# DNVT3.net
KiCad netlist of a schematic drawn in EAGLE
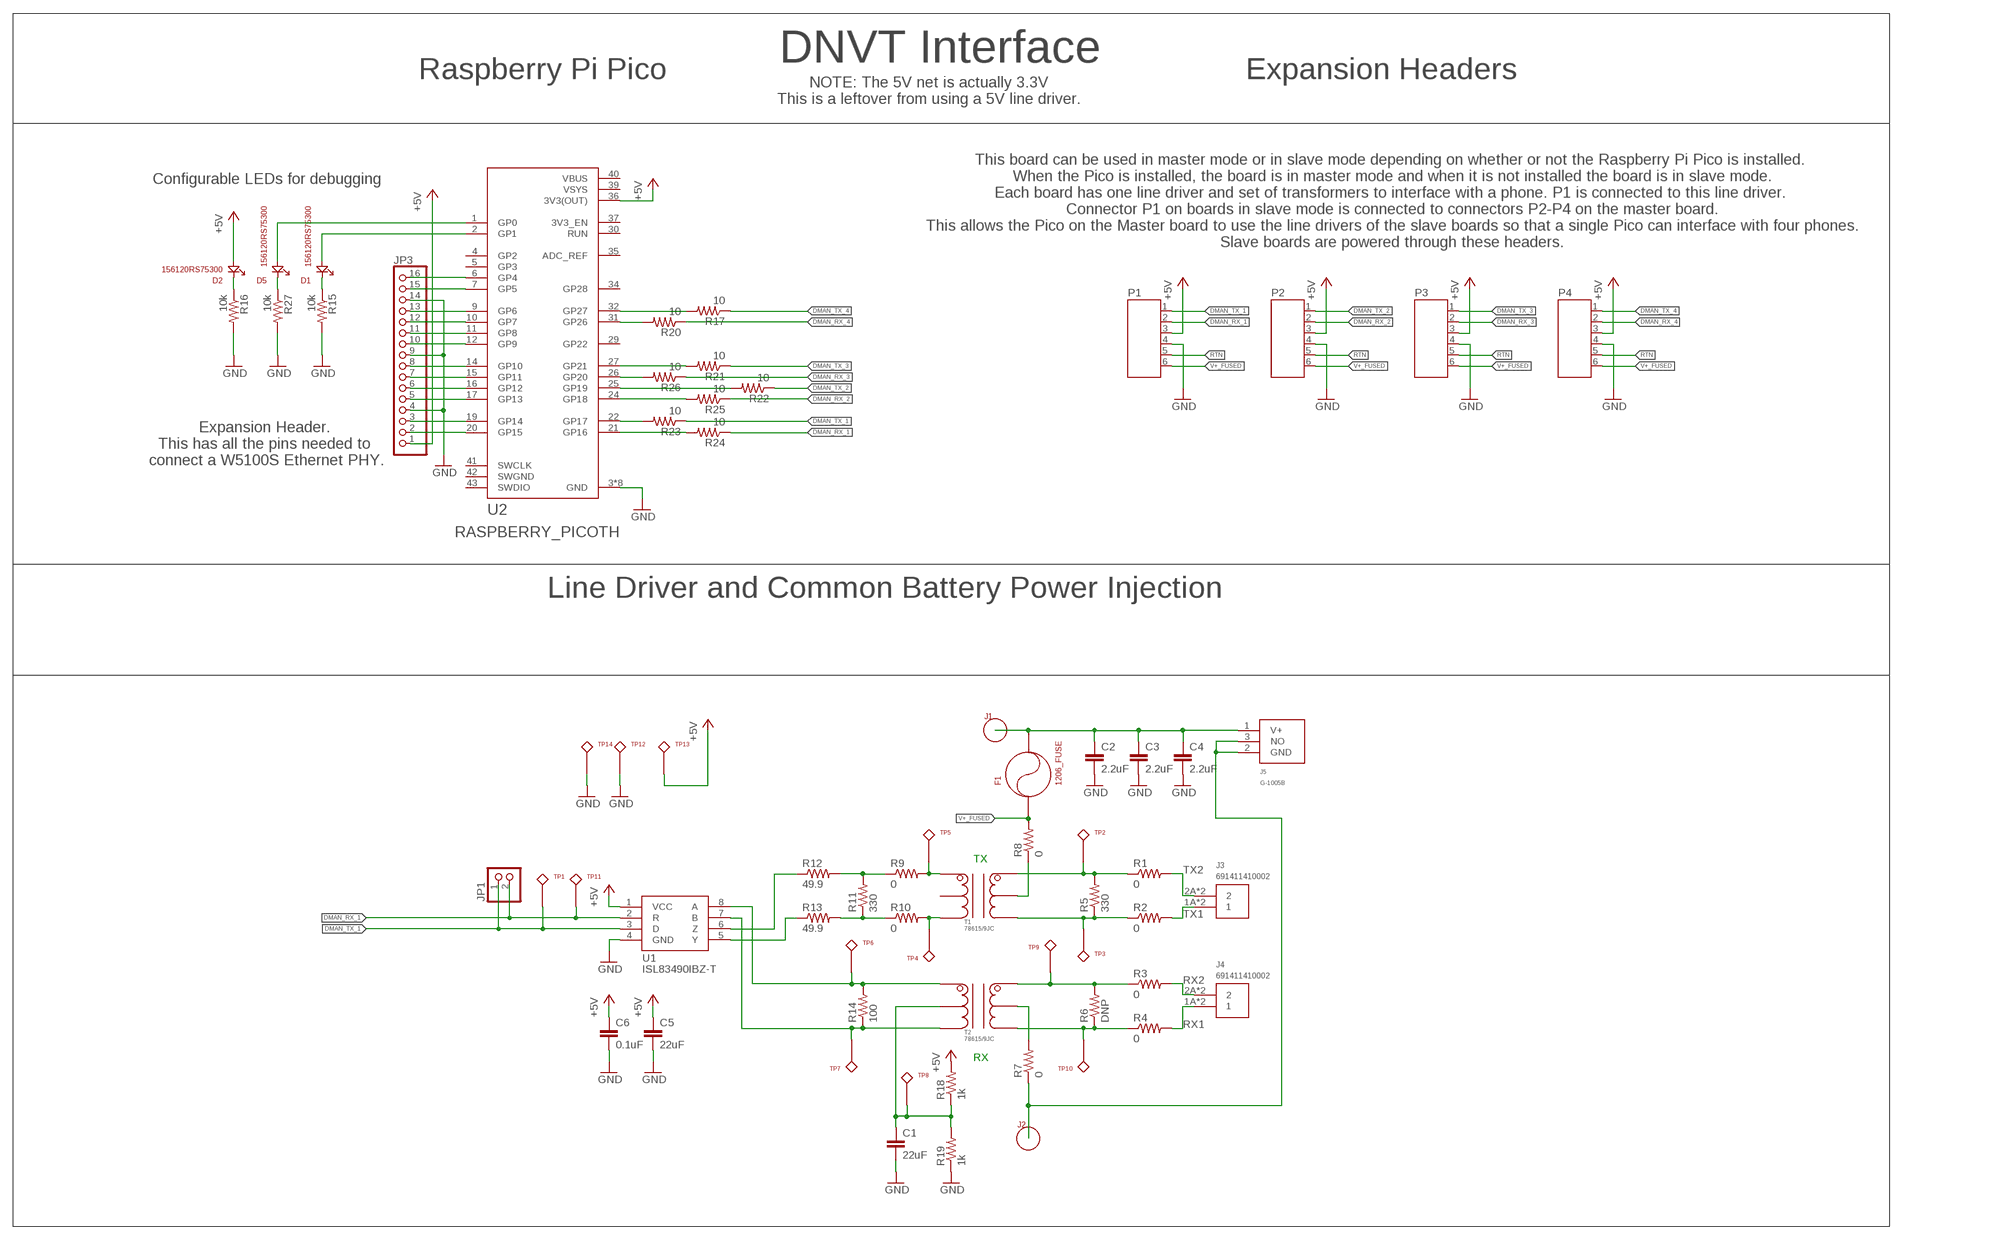
[diagram p0: schematic, sheet 1]

(export (version "E")
  (design (tool "Eeschema 10.0.6"))
  (components
    (comp (ref "C1")
      (value "22uF")
      (footprint "eagle-import:1210")
      (libsource (lib "eagle-import") (part "1210_CAPACITOR"))
    )
    (comp (ref "C2")
      (value "2.2uF")
      (footprint "eagle-import:1210")
      (libsource (lib "eagle-import") (part "1210_CAPACITOR"))
    )
    (comp (ref "C3")
      (value "2.2uF")
      (footprint "eagle-import:1210")
      (libsource (lib "eagle-import") (part "1210_CAPACITOR"))
    )
    (comp (ref "C4")
      (value "2.2uF")
      (footprint "eagle-import:1210")
      (libsource (lib "eagle-import") (part "1210_CAPACITOR"))
    )
    (comp (ref "C5")
      (value "22uF")
      (footprint "eagle-import:1210")
      (libsource (lib "eagle-import") (part "1210_CAPACITOR"))
    )
    (comp (ref "C6")
      (value "0.1uF")
      (footprint "eagle-import:0603")
      (libsource (lib "eagle-import") (part "0603_CAPACITOR"))
    )
    (comp (ref "D1")
      (value "156120RS75300")
      (footprint "eagle-import:1206_REV")
      (fields (field (name "PARTNO") "732-5031-1-ND"))
      (libsource (lib "eagle-import") (part "156120RS75300"))
    )
    (comp (ref "D2")
      (value "156120RS75300")
      (footprint "eagle-import:1206_REV")
      (fields (field (name "PARTNO") "732-5031-1-ND"))
      (libsource (lib "eagle-import") (part "156120RS75300"))
    )
    (comp (ref "D5")
      (value "156120RS75300")
      (footprint "eagle-import:1206_REV")
      (fields (field (name "PARTNO") "732-5031-1-ND"))
      (libsource (lib "eagle-import") (part "156120RS75300"))
    )
    (comp (ref "F1")
      (value "1206_FUSE")
      (footprint "eagle-import:1206")
      (libsource (lib "eagle-import") (part "1206_FUSE"))
    )
    (comp (ref "J1")
      (value "BANANA")
      (footprint "eagle-import:BANANA")
      (fields (field (name "PARTNO") "36-575-4-ND"))
      (libsource (lib "eagle-import") (part "BANANA"))
    )
    (comp (ref "J2")
      (value "BANANA")
      (footprint "eagle-import:BANANA")
      (fields (field (name "PARTNO") "36-575-4-ND"))
      (libsource (lib "eagle-import") (part "BANANA"))
    )
    (comp (ref "J3")
      (value "691411410002")
      (footprint "eagle-import:691411410002")
      (fields (field (name "PARTNO") "732-11084-ND"))
      (libsource (lib "eagle-import") (part "691411410002"))
    )
    (comp (ref "J4")
      (value "691411410002")
      (footprint "eagle-import:691411410002")
      (fields (field (name "PARTNO") "732-11084-ND"))
      (libsource (lib "eagle-import") (part "691411410002"))
    )
    (comp (ref "J5")
      (value "G-1005B")
      (footprint "eagle-import:G-1005B")
      (fields (field (name "PARTNO") "1939-G-1005B-ND"))
      (libsource (lib "eagle-import") (part "G-1005B"))
    )
    (comp (ref "JP1")
      (value "PINHD-1X2")
      (footprint "eagle-import:1X02")
      (libsource (lib "eagle-import") (part "PINHD-1X2"))
    )
    (comp (ref "JP3")
      (value "PINHD-1X16")
      (footprint "eagle-import:1X16")
      (libsource (lib "eagle-import") (part "PINHD-1X16"))
    )
    (comp (ref "P1")
      (value "JST-PH6")
      (footprint "eagle-import:JST-PH6")
      (libsource (lib "eagle-import") (part "JST-PH6"))
    )
    (comp (ref "P2")
      (value "JST-PH6")
      (footprint "eagle-import:JST-PH6")
      (libsource (lib "eagle-import") (part "JST-PH6"))
    )
    (comp (ref "P3")
      (value "JST-PH6")
      (footprint "eagle-import:JST-PH6")
      (libsource (lib "eagle-import") (part "JST-PH6"))
    )
    (comp (ref "P4")
      (value "JST-PH6")
      (footprint "eagle-import:JST-PH6")
      (libsource (lib "eagle-import") (part "JST-PH6"))
    )
    (comp (ref "R1")
      (value "0")
      (footprint "eagle-import:R0805")
      (libsource (lib "eagle-import") (part "R-US_R0805"))
    )
    (comp (ref "R2")
      (value "0")
      (footprint "eagle-import:R0805")
      (libsource (lib "eagle-import") (part "R-US_R0805"))
    )
    (comp (ref "R3")
      (value "0")
      (footprint "eagle-import:R0805")
      (libsource (lib "eagle-import") (part "R-US_R0805"))
    )
    (comp (ref "R4")
      (value "0")
      (footprint "eagle-import:R0805")
      (libsource (lib "eagle-import") (part "R-US_R0805"))
    )
    (comp (ref "R5")
      (value "330")
      (footprint "eagle-import:R0805")
      (libsource (lib "eagle-import") (part "R-US_R0805"))
    )
    (comp (ref "R6")
      (value "DNP")
      (footprint "eagle-import:R0805")
      (libsource (lib "eagle-import") (part "R-US_R0805"))
    )
    (comp (ref "R7")
      (value "0")
      (footprint "eagle-import:R0805")
      (libsource (lib "eagle-import") (part "R-US_R0805"))
    )
    (comp (ref "R8")
      (value "0")
      (footprint "eagle-import:R0805")
      (libsource (lib "eagle-import") (part "R-US_R0805"))
    )
    (comp (ref "R9")
      (value "0")
      (footprint "eagle-import:R0805")
      (libsource (lib "eagle-import") (part "R-US_R0805"))
    )
    (comp (ref "R10")
      (value "0")
      (footprint "eagle-import:R0805")
      (libsource (lib "eagle-import") (part "R-US_R0805"))
    )
    (comp (ref "R11")
      (value "330")
      (footprint "eagle-import:R0805")
      (libsource (lib "eagle-import") (part "R-US_R0805"))
    )
    (comp (ref "R12")
      (value "49.9")
      (footprint "eagle-import:R0805")
      (libsource (lib "eagle-import") (part "R-US_R0805"))
    )
    (comp (ref "R13")
      (value "49.9")
      (footprint "eagle-import:R0805")
      (libsource (lib "eagle-import") (part "R-US_R0805"))
    )
    (comp (ref "R14")
      (value "100")
      (footprint "eagle-import:1206")
      (libsource (lib "eagle-import") (part "1206_RESISTOR"))
    )
    (comp (ref "R15")
      (value "10k")
      (footprint "eagle-import:0603")
      (libsource (lib "eagle-import") (part "0603_RESISTOR"))
    )
    (comp (ref "R16")
      (value "10k")
      (footprint "eagle-import:0603")
      (libsource (lib "eagle-import") (part "0603_RESISTOR"))
    )
    (comp (ref "R17")
      (value "10")
      (footprint "eagle-import:0603")
      (libsource (lib "eagle-import") (part "0603_RESISTOR"))
    )
    (comp (ref "R18")
      (value "1k")
      (footprint "eagle-import:0603")
      (libsource (lib "eagle-import") (part "0603_RESISTOR"))
    )
    (comp (ref "R19")
      (value "1k")
      (footprint "eagle-import:0603")
      (libsource (lib "eagle-import") (part "0603_RESISTOR"))
    )
    (comp (ref "R20")
      (value "10")
      (footprint "eagle-import:0603")
      (libsource (lib "eagle-import") (part "0603_RESISTOR"))
    )
    (comp (ref "R21")
      (value "10")
      (footprint "eagle-import:0603")
      (libsource (lib "eagle-import") (part "0603_RESISTOR"))
    )
    (comp (ref "R22")
      (value "10")
      (footprint "eagle-import:0603")
      (libsource (lib "eagle-import") (part "0603_RESISTOR"))
    )
    (comp (ref "R23")
      (value "10")
      (footprint "eagle-import:0603")
      (libsource (lib "eagle-import") (part "0603_RESISTOR"))
    )
    (comp (ref "R24")
      (value "10")
      (footprint "eagle-import:0603")
      (libsource (lib "eagle-import") (part "0603_RESISTOR"))
    )
    (comp (ref "R25")
      (value "10")
      (footprint "eagle-import:0603")
      (libsource (lib "eagle-import") (part "0603_RESISTOR"))
    )
    (comp (ref "R26")
      (value "10")
      (footprint "eagle-import:0603")
      (libsource (lib "eagle-import") (part "0603_RESISTOR"))
    )
    (comp (ref "R27")
      (value "10k")
      (footprint "eagle-import:0603")
      (libsource (lib "eagle-import") (part "0603_RESISTOR"))
    )
    (comp (ref "T1")
      (value "78615/9JC")
      (footprint "eagle-import:786")
      (fields (field (name "PARTNO") "811-2423-ND"))
      (libsource (lib "eagle-import") (part "78615/9JC"))
    )
    (comp (ref "T2")
      (value "78615/9JC")
      (footprint "eagle-import:786")
      (fields (field (name "PARTNO") "811-2423-ND"))
      (libsource (lib "eagle-import") (part "78615/9JC"))
    )
    (comp (ref "TP1")
      (value "5001")
      (footprint "eagle-import:5001")
      (fields (field (name "PARTNO") "36-5001-ND"))
      (libsource (lib "eagle-import") (part "5001"))
    )
    (comp (ref "TP2")
      (value "5002")
      (footprint "eagle-import:5001")
      (fields (field (name "PARTNO") "36-5002-ND"))
      (libsource (lib "eagle-import") (part "5002"))
    )
    (comp (ref "TP3")
      (value "5002")
      (footprint "eagle-import:5001")
      (fields (field (name "PARTNO") "36-5002-ND"))
      (libsource (lib "eagle-import") (part "5002"))
    )
    (comp (ref "TP4")
      (value "5002")
      (footprint "eagle-import:5001")
      (fields (field (name "PARTNO") "36-5002-ND"))
      (libsource (lib "eagle-import") (part "5002"))
    )
    (comp (ref "TP5")
      (value "5002")
      (footprint "eagle-import:5001")
      (fields (field (name "PARTNO") "36-5002-ND"))
      (libsource (lib "eagle-import") (part "5002"))
    )
    (comp (ref "TP6")
      (value "5002")
      (footprint "eagle-import:5001")
      (fields (field (name "PARTNO") "36-5002-ND"))
      (libsource (lib "eagle-import") (part "5002"))
    )
    (comp (ref "TP7")
      (value "5002")
      (footprint "eagle-import:5001")
      (fields (field (name "PARTNO") "36-5002-ND"))
      (libsource (lib "eagle-import") (part "5002"))
    )
    (comp (ref "TP8")
      (value "5002")
      (footprint "eagle-import:5001")
      (fields (field (name "PARTNO") "36-5002-ND"))
      (libsource (lib "eagle-import") (part "5002"))
    )
    (comp (ref "TP9")
      (value "5002")
      (footprint "eagle-import:5001")
      (fields (field (name "PARTNO") "36-5002-ND"))
      (libsource (lib "eagle-import") (part "5002"))
    )
    (comp (ref "TP10")
      (value "5002")
      (footprint "eagle-import:5001")
      (fields (field (name "PARTNO") "36-5002-ND"))
      (libsource (lib "eagle-import") (part "5002"))
    )
    (comp (ref "TP11")
      (value "5001")
      (footprint "eagle-import:5001")
      (fields (field (name "PARTNO") "36-5001-ND"))
      (libsource (lib "eagle-import") (part "5001"))
    )
    (comp (ref "TP12")
      (value "5001")
      (footprint "eagle-import:5001")
      (fields (field (name "PARTNO") "36-5001-ND"))
      (libsource (lib "eagle-import") (part "5001"))
    )
    (comp (ref "TP13")
      (value "5001")
      (footprint "eagle-import:5001")
      (fields (field (name "PARTNO") "36-5001-ND"))
      (libsource (lib "eagle-import") (part "5001"))
    )
    (comp (ref "TP14")
      (value "5001")
      (footprint "eagle-import:5001")
      (fields (field (name "PARTNO") "36-5001-ND"))
      (libsource (lib "eagle-import") (part "5001"))
    )
    (comp (ref "U1")
      (value "ISL83490IBZ-T")
      (footprint "eagle-import:SOIC8")
      (fields (field (name "PARTNO") "ISL83490IBZ-TCT-ND"))
      (libsource (lib "eagle-import") (part "ISL83490IBZ-T"))
    )
    (comp (ref "U2")
      (value "RASPBERRY_PICOTH")
      (footprint "eagle-import:PICO-PKG-TH")
      (libsource (lib "eagle-import") (part "RASPBERRY_PICOTH"))
    )
  )
  (nets
    (net (code "1") (name "+5V") (class "Default")
      (node (ref "C5") (pin "1") (pinfunction "1_1") (pintype "passive"))
      (node (ref "C6") (pin "1") (pinfunction "1_1") (pintype "passive"))
      (node (ref "D2") (pin "A") (pinfunction "A_A") (pintype "bidirectional"))
      (node (ref "JP3") (pin "1") (pinfunction "1_1") (pintype "passive"))
      (node (ref "P1") (pin "3") (pinfunction "3_3") (pintype "passive"))
      (node (ref "P2") (pin "3") (pinfunction "3_3") (pintype "passive"))
      (node (ref "P3") (pin "3") (pinfunction "3_3") (pintype "passive"))
      (node (ref "P4") (pin "3") (pinfunction "3_3") (pintype "passive"))
      (node (ref "R18") (pin "2") (pinfunction "2_2") (pintype "passive"))
      (node (ref "TP13") (pin "P$1") (pinfunction "P$1_P$1") (pintype "bidirectional"))
      (node (ref "U1") (pin "1") (pinfunction "VCC_1") (pintype "bidirectional"))
      (node (ref "U2") (pin "36") (pinfunction "3V3(OUT)_36") (pintype "power_in"))
    )
    (net (code "2") (name "/RX1") (class "Default")
      (node (ref "J4") (pin "1A") (pinfunction "1_1A") (pintype "bidirectional"))
      (node (ref "J4") (pin "1B") (pinfunction "1_1B") (pintype "bidirectional"))
      (node (ref "R4") (pin "2") (pinfunction "2_2") (pintype "passive"))
    )
    (net (code "3") (name "/RX2") (class "Default")
      (node (ref "J4") (pin "2A") (pinfunction "2_2A") (pintype "bidirectional"))
      (node (ref "J4") (pin "2B") (pinfunction "2_2B") (pintype "bidirectional"))
      (node (ref "R3") (pin "2") (pinfunction "2_2") (pintype "passive"))
    )
    (net (code "4") (name "/SWGND") (class "Default")
      (node (ref "U2") (pin "42") (pinfunction "SWGND_42") (pintype "power_in"))
    )
    (net (code "5") (name "/TX1") (class "Default")
      (node (ref "J3") (pin "1A") (pinfunction "1_1A") (pintype "bidirectional"))
      (node (ref "J3") (pin "1B") (pinfunction "1_1B") (pintype "bidirectional"))
      (node (ref "R2") (pin "2") (pinfunction "2_2") (pintype "passive"))
    )
    (net (code "6") (name "/TX2") (class "Default")
      (node (ref "J3") (pin "2A") (pinfunction "2_2A") (pintype "bidirectional"))
      (node (ref "J3") (pin "2B") (pinfunction "2_2B") (pintype "bidirectional"))
      (node (ref "R1") (pin "2") (pinfunction "2_2") (pintype "passive"))
    )
    (net (code "7") (name "/VBUS") (class "Default")
      (node (ref "U2") (pin "40") (pinfunction "VBUS_40") (pintype "power_in"))
    )
    (net (code "8") (name "/VSYS") (class "Default")
      (node (ref "U2") (pin "39") (pinfunction "VSYS_39") (pintype "power_in"))
    )
    (net (code "9") (name "DMAN_RX_1") (class "Default")
      (node (ref "JP1") (pin "2") (pinfunction "2_2") (pintype "passive"))
      (node (ref "P1") (pin "2") (pinfunction "2_2") (pintype "passive"))
      (node (ref "R24") (pin "1") (pinfunction "1_1") (pintype "passive"))
      (node (ref "TP11") (pin "P$1") (pinfunction "P$1_P$1") (pintype "bidirectional"))
      (node (ref "U1") (pin "2") (pinfunction "R_2") (pintype "bidirectional"))
    )
    (net (code "10") (name "DMAN_RX_2") (class "Default")
      (node (ref "P2") (pin "2") (pinfunction "2_2") (pintype "passive"))
      (node (ref "R25") (pin "1") (pinfunction "1_1") (pintype "passive"))
    )
    (net (code "11") (name "DMAN_RX_3") (class "Default")
      (node (ref "P3") (pin "2") (pinfunction "2_2") (pintype "passive"))
      (node (ref "R26") (pin "1") (pinfunction "1_1") (pintype "passive"))
    )
    (net (code "12") (name "DMAN_RX_4") (class "Default")
      (node (ref "P4") (pin "2") (pinfunction "2_2") (pintype "passive"))
      (node (ref "R20") (pin "1") (pinfunction "1_1") (pintype "passive"))
    )
    (net (code "13") (name "DMAN_TX_1") (class "Default")
      (node (ref "JP1") (pin "1") (pinfunction "1_1") (pintype "passive"))
      (node (ref "P1") (pin "1") (pinfunction "1_1") (pintype "passive"))
      (node (ref "R23") (pin "1") (pinfunction "1_1") (pintype "passive"))
      (node (ref "TP1") (pin "P$1") (pinfunction "P$1_P$1") (pintype "bidirectional"))
      (node (ref "U1") (pin "3") (pinfunction "D_3") (pintype "bidirectional"))
    )
    (net (code "14") (name "DMAN_TX_2") (class "Default")
      (node (ref "P2") (pin "1") (pinfunction "1_1") (pintype "passive"))
      (node (ref "R22") (pin "1") (pinfunction "1_1") (pintype "passive"))
    )
    (net (code "15") (name "DMAN_TX_3") (class "Default")
      (node (ref "P3") (pin "1") (pinfunction "1_1") (pintype "passive"))
      (node (ref "R21") (pin "1") (pinfunction "1_1") (pintype "passive"))
    )
    (net (code "16") (name "DMAN_TX_4") (class "Default")
      (node (ref "P4") (pin "1") (pinfunction "1_1") (pintype "passive"))
      (node (ref "R17") (pin "1") (pinfunction "1_1") (pintype "passive"))
    )
    (net (code "17") (name "GND") (class "Default")
      (node (ref "C1") (pin "2") (pinfunction "2_2") (pintype "passive"))
      (node (ref "C2") (pin "2") (pinfunction "2_2") (pintype "passive"))
      (node (ref "C3") (pin "2") (pinfunction "2_2") (pintype "passive"))
      (node (ref "C4") (pin "2") (pinfunction "2_2") (pintype "passive"))
      (node (ref "C5") (pin "2") (pinfunction "2_2") (pintype "passive"))
      (node (ref "C6") (pin "2") (pinfunction "2_2") (pintype "passive"))
      (node (ref "JP3") (pin "14") (pinfunction "14_14") (pintype "passive"))
      (node (ref "JP3") (pin "4") (pinfunction "4_4") (pintype "passive"))
      (node (ref "JP3") (pin "9") (pinfunction "9_9") (pintype "passive"))
      (node (ref "P1") (pin "4") (pinfunction "4_4") (pintype "passive"))
      (node (ref "P2") (pin "4") (pinfunction "4_4") (pintype "passive"))
      (node (ref "P3") (pin "4") (pinfunction "4_4") (pintype "passive"))
      (node (ref "P4") (pin "4") (pinfunction "4_4") (pintype "passive"))
      (node (ref "R15") (pin "2") (pinfunction "2_2") (pintype "passive"))
      (node (ref "R16") (pin "2") (pinfunction "2_2") (pintype "passive"))
      (node (ref "R19") (pin "1") (pinfunction "1_1") (pintype "passive"))
      (node (ref "R27") (pin "2") (pinfunction "2_2") (pintype "passive"))
      (node (ref "TP12") (pin "P$1") (pinfunction "P$1_P$1") (pintype "bidirectional"))
      (node (ref "TP14") (pin "P$1") (pinfunction "P$1_P$1") (pintype "bidirectional"))
      (node (ref "U1") (pin "4") (pinfunction "GND_4") (pintype "bidirectional"))
      (node (ref "U2") (pin "13") (pinfunction "GND_13") (pintype "power_in"))
      (node (ref "U2") (pin "18") (pinfunction "GND_18") (pintype "power_in"))
      (node (ref "U2") (pin "23") (pinfunction "GND_23") (pintype "power_in"))
      (node (ref "U2") (pin "28") (pinfunction "GND_28") (pintype "power_in"))
      (node (ref "U2") (pin "3") (pinfunction "GND_3") (pintype "power_in"))
      (node (ref "U2") (pin "33") (pinfunction "GND_33") (pintype "power_in"))
      (node (ref "U2") (pin "38") (pinfunction "GND_38") (pintype "power_in"))
      (node (ref "U2") (pin "8") (pinfunction "GND_8") (pintype "power_in"))
    )
    (net (code "18") (name "Net-(C1-Pad1)") (class "Default")
      (node (ref "C1") (pin "1") (pinfunction "1_1") (pintype "passive"))
      (node (ref "R18") (pin "1") (pinfunction "1_1") (pintype "passive"))
      (node (ref "R19") (pin "2") (pinfunction "2_2") (pintype "passive"))
      (node (ref "T2") (pin "2") (pinfunction "2_2") (pintype "bidirectional"))
      (node (ref "TP8") (pin "P$1") (pinfunction "P$1_P$1") (pintype "bidirectional"))
    )
    (net (code "19") (name "Net-(D1-PadK)") (class "Default")
      (node (ref "D1") (pin "K") (pinfunction "K_K") (pintype "bidirectional"))
      (node (ref "R15") (pin "1") (pinfunction "1_1") (pintype "passive"))
    )
    (net (code "20") (name "Net-(D2-PadK)") (class "Default")
      (node (ref "D2") (pin "K") (pinfunction "K_K") (pintype "bidirectional"))
      (node (ref "R16") (pin "1") (pinfunction "1_1") (pintype "passive"))
    )
    (net (code "21") (name "Net-(D5-PadK)") (class "Default")
      (node (ref "D5") (pin "K") (pinfunction "K_K") (pintype "bidirectional"))
      (node (ref "R27") (pin "1") (pinfunction "1_1") (pintype "passive"))
    )
    (net (code "22") (name "Net-(F1-P$2)") (class "Default")
      (node (ref "C2") (pin "1") (pinfunction "1_1") (pintype "passive"))
      (node (ref "C3") (pin "1") (pinfunction "1_1") (pintype "passive"))
      (node (ref "C4") (pin "1") (pinfunction "1_1") (pintype "passive"))
      (node (ref "F1") (pin "2") (pinfunction "P$2_2") (pintype "bidirectional"))
      (node (ref "J1") (pin "P$1") (pinfunction "P$1_P$1") (pintype "bidirectional"))
      (node (ref "J5") (pin "1") (pinfunction "V+_1") (pintype "bidirectional"))
    )
    (net (code "23") (name "Net-(R1-Pad1)") (class "Default")
      (node (ref "R1") (pin "1") (pinfunction "1_1") (pintype "passive"))
      (node (ref "R5") (pin "2") (pinfunction "2_2") (pintype "passive"))
      (node (ref "T1") (pin "6") (pinfunction "6_6") (pintype "bidirectional"))
      (node (ref "TP2") (pin "P$1") (pinfunction "P$1_P$1") (pintype "bidirectional"))
    )
    (net (code "24") (name "Net-(R2-Pad1)") (class "Default")
      (node (ref "R2") (pin "1") (pinfunction "1_1") (pintype "passive"))
      (node (ref "R5") (pin "1") (pinfunction "1_1") (pintype "passive"))
      (node (ref "T1") (pin "4") (pinfunction "4_4") (pintype "bidirectional"))
      (node (ref "TP3") (pin "P$1") (pinfunction "P$1_P$1") (pintype "bidirectional"))
    )
    (net (code "25") (name "Net-(R3-Pad1)") (class "Default")
      (node (ref "R3") (pin "1") (pinfunction "1_1") (pintype "passive"))
      (node (ref "R6") (pin "2") (pinfunction "2_2") (pintype "passive"))
      (node (ref "T2") (pin "6") (pinfunction "6_6") (pintype "bidirectional"))
      (node (ref "TP9") (pin "P$1") (pinfunction "P$1_P$1") (pintype "bidirectional"))
    )
    (net (code "26") (name "Net-(R4-Pad1)") (class "Default")
      (node (ref "R4") (pin "1") (pinfunction "1_1") (pintype "passive"))
      (node (ref "R6") (pin "1") (pinfunction "1_1") (pintype "passive"))
      (node (ref "T2") (pin "4") (pinfunction "4_4") (pintype "bidirectional"))
      (node (ref "TP10") (pin "P$1") (pinfunction "P$1_P$1") (pintype "bidirectional"))
    )
    (net (code "27") (name "Net-(R7-Pad2)") (class "Default")
      (node (ref "R7") (pin "2") (pinfunction "2_2") (pintype "passive"))
      (node (ref "T2") (pin "5") (pinfunction "5_5") (pintype "bidirectional"))
    )
    (net (code "28") (name "Net-(R8-Pad1)") (class "Default")
      (node (ref "R8") (pin "1") (pinfunction "1_1") (pintype "passive"))
      (node (ref "T1") (pin "5") (pinfunction "5_5") (pintype "bidirectional"))
    )
    (net (code "29") (name "Net-(R9-Pad2)") (class "Default")
      (node (ref "R9") (pin "2") (pinfunction "2_2") (pintype "passive"))
      (node (ref "T1") (pin "1") (pinfunction "1_1") (pintype "bidirectional"))
      (node (ref "TP5") (pin "P$1") (pinfunction "P$1_P$1") (pintype "bidirectional"))
    )
    (net (code "30") (name "Net-(R10-Pad1)") (class "Default")
      (node (ref "R10") (pin "1") (pinfunction "1_1") (pintype "passive"))
      (node (ref "R11") (pin "1") (pinfunction "1_1") (pintype "passive"))
      (node (ref "R13") (pin "2") (pinfunction "2_2") (pintype "passive"))
    )
    (net (code "31") (name "Net-(R10-Pad2)") (class "Default")
      (node (ref "R10") (pin "2") (pinfunction "2_2") (pintype "passive"))
      (node (ref "T1") (pin "3") (pinfunction "3_3") (pintype "bidirectional"))
      (node (ref "TP4") (pin "P$1") (pinfunction "P$1_P$1") (pintype "bidirectional"))
    )
    (net (code "32") (name "Net-(R11-Pad2)") (class "Default")
      (node (ref "R11") (pin "2") (pinfunction "2_2") (pintype "passive"))
      (node (ref "R12") (pin "2") (pinfunction "2_2") (pintype "passive"))
      (node (ref "R9") (pin "1") (pinfunction "1_1") (pintype "passive"))
    )
    (net (code "33") (name "Net-(U1-A)") (class "Default")
      (node (ref "R14") (pin "2") (pinfunction "2_2") (pintype "passive"))
      (node (ref "T2") (pin "1") (pinfunction "1_1") (pintype "bidirectional"))
      (node (ref "TP6") (pin "P$1") (pinfunction "P$1_P$1") (pintype "bidirectional"))
      (node (ref "U1") (pin "8") (pinfunction "A_8") (pintype "bidirectional"))
    )
    (net (code "34") (name "Net-(U1-B)") (class "Default")
      (node (ref "R14") (pin "1") (pinfunction "1_1") (pintype "passive"))
      (node (ref "T2") (pin "3") (pinfunction "3_3") (pintype "bidirectional"))
      (node (ref "TP7") (pin "P$1") (pinfunction "P$1_P$1") (pintype "bidirectional"))
      (node (ref "U1") (pin "7") (pinfunction "B_7") (pintype "bidirectional"))
    )
    (net (code "35") (name "Net-(U1-Y)") (class "Default")
      (node (ref "R13") (pin "1") (pinfunction "1_1") (pintype "passive"))
      (node (ref "U1") (pin "5") (pinfunction "Y_5") (pintype "bidirectional"))
    )
    (net (code "36") (name "Net-(U1-Z)") (class "Default")
      (node (ref "R12") (pin "1") (pinfunction "1_1") (pintype "passive"))
      (node (ref "U1") (pin "6") (pinfunction "Z_6") (pintype "bidirectional"))
    )
    (net (code "37") (name "Net-(U2-GP0)") (class "Default")
      (node (ref "D5") (pin "A") (pinfunction "A_A") (pintype "bidirectional"))
      (node (ref "U2") (pin "1") (pinfunction "GP0_1") (pintype "bidirectional"))
    )
    (net (code "38") (name "Net-(U2-GP1)") (class "Default")
      (node (ref "D1") (pin "A") (pinfunction "A_A") (pintype "bidirectional"))
      (node (ref "U2") (pin "2") (pinfunction "GP1_2") (pintype "bidirectional"))
    )
    (net (code "39") (name "Net-(U2-GP4)") (class "Default")
      (node (ref "JP3") (pin "16") (pinfunction "16_16") (pintype "passive"))
      (node (ref "U2") (pin "6") (pinfunction "GP4_6") (pintype "bidirectional"))
    )
    (net (code "40") (name "Net-(U2-GP5)") (class "Default")
      (node (ref "JP3") (pin "15") (pinfunction "15_15") (pintype "passive"))
      (node (ref "U2") (pin "7") (pinfunction "GP5_7") (pintype "bidirectional"))
    )
    (net (code "41") (name "Net-(U2-GP6)") (class "Default")
      (node (ref "JP3") (pin "13") (pinfunction "13_13") (pintype "passive"))
      (node (ref "U2") (pin "9") (pinfunction "GP6_9") (pintype "bidirectional"))
    )
    (net (code "42") (name "Net-(U2-GP7)") (class "Default")
      (node (ref "JP3") (pin "12") (pinfunction "12_12") (pintype "passive"))
      (node (ref "U2") (pin "10") (pinfunction "GP7_10") (pintype "bidirectional"))
    )
    (net (code "43") (name "Net-(U2-GP8)") (class "Default")
      (node (ref "JP3") (pin "11") (pinfunction "11_11") (pintype "passive"))
      (node (ref "U2") (pin "11") (pinfunction "GP8_11") (pintype "bidirectional"))
    )
    (net (code "44") (name "Net-(U2-GP9)") (class "Default")
      (node (ref "JP3") (pin "10") (pinfunction "10_10") (pintype "passive"))
      (node (ref "U2") (pin "12") (pinfunction "GP9_12") (pintype "bidirectional"))
    )
    (net (code "45") (name "Net-(U2-GP10)") (class "Default")
      (node (ref "JP3") (pin "8") (pinfunction "8_8") (pintype "passive"))
      (node (ref "U2") (pin "14") (pinfunction "GP10_14") (pintype "bidirectional"))
    )
    (net (code "46") (name "Net-(U2-GP11)") (class "Default")
      (node (ref "JP3") (pin "7") (pinfunction "7_7") (pintype "passive"))
      (node (ref "U2") (pin "15") (pinfunction "GP11_15") (pintype "bidirectional"))
    )
    (net (code "47") (name "Net-(U2-GP12)") (class "Default")
      (node (ref "JP3") (pin "6") (pinfunction "6_6") (pintype "passive"))
      (node (ref "U2") (pin "16") (pinfunction "GP12_16") (pintype "bidirectional"))
    )
    (net (code "48") (name "Net-(U2-GP13)") (class "Default")
      (node (ref "JP3") (pin "5") (pinfunction "5_5") (pintype "passive"))
      (node (ref "U2") (pin "17") (pinfunction "GP13_17") (pintype "bidirectional"))
    )
    (net (code "49") (name "Net-(U2-GP14)") (class "Default")
      (node (ref "JP3") (pin "3") (pinfunction "3_3") (pintype "passive"))
      (node (ref "U2") (pin "19") (pinfunction "GP14_19") (pintype "bidirectional"))
    )
    (net (code "50") (name "Net-(U2-GP15)") (class "Default")
      (node (ref "JP3") (pin "2") (pinfunction "2_2") (pintype "passive"))
      (node (ref "U2") (pin "20") (pinfunction "GP15_20") (pintype "bidirectional"))
    )
    (net (code "51") (name "Net-(U2-GP16)") (class "Default")
      (node (ref "R24") (pin "2") (pinfunction "2_2") (pintype "passive"))
      (node (ref "U2") (pin "21") (pinfunction "GP16_21") (pintype "bidirectional"))
    )
    (net (code "52") (name "Net-(U2-GP17)") (class "Default")
      (node (ref "R23") (pin "2") (pinfunction "2_2") (pintype "passive"))
      (node (ref "U2") (pin "22") (pinfunction "GP17_22") (pintype "bidirectional"))
    )
    (net (code "53") (name "Net-(U2-GP18)") (class "Default")
      (node (ref "R25") (pin "2") (pinfunction "2_2") (pintype "passive"))
      (node (ref "U2") (pin "24") (pinfunction "GP18_24") (pintype "bidirectional"))
    )
    (net (code "54") (name "Net-(U2-GP19)") (class "Default")
      (node (ref "R22") (pin "2") (pinfunction "2_2") (pintype "passive"))
      (node (ref "U2") (pin "25") (pinfunction "GP19_25") (pintype "bidirectional"))
    )
    (net (code "55") (name "Net-(U2-GP20)") (class "Default")
      (node (ref "R26") (pin "2") (pinfunction "2_2") (pintype "passive"))
      (node (ref "U2") (pin "26") (pinfunction "GP20_26") (pintype "bidirectional"))
    )
    (net (code "56") (name "Net-(U2-GP21)") (class "Default")
      (node (ref "R21") (pin "2") (pinfunction "2_2") (pintype "passive"))
      (node (ref "U2") (pin "27") (pinfunction "GP21_27") (pintype "bidirectional"))
    )
    (net (code "57") (name "Net-(U2-GP26)") (class "Default")
      (node (ref "R20") (pin "2") (pinfunction "2_2") (pintype "passive"))
      (node (ref "U2") (pin "31") (pinfunction "GP26_31") (pintype "bidirectional"))
    )
    (net (code "58") (name "Net-(U2-GP27)") (class "Default")
      (node (ref "R17") (pin "2") (pinfunction "2_2") (pintype "passive"))
      (node (ref "U2") (pin "32") (pinfunction "GP27_32") (pintype "bidirectional"))
    )
    (net (code "59") (name "RTN") (class "Default")
      (node (ref "J2") (pin "P$1") (pinfunction "P$1_P$1") (pintype "bidirectional"))
      (node (ref "J5") (pin "2") (pinfunction "GND_2") (pintype "bidirectional"))
      (node (ref "J5") (pin "3") (pinfunction "NO_3") (pintype "bidirectional"))
      (node (ref "P1") (pin "5") (pinfunction "5_5") (pintype "passive"))
      (node (ref "P2") (pin "5") (pinfunction "5_5") (pintype "passive"))
      (node (ref "P3") (pin "5") (pinfunction "5_5") (pintype "passive"))
      (node (ref "P4") (pin "5") (pinfunction "5_5") (pintype "passive"))
      (node (ref "R7") (pin "1") (pinfunction "1_1") (pintype "passive"))
    )
    (net (code "60") (name "V+_FUSED") (class "Default")
      (node (ref "F1") (pin "1") (pinfunction "P$1_1") (pintype "bidirectional"))
      (node (ref "P1") (pin "6") (pinfunction "6_6") (pintype "passive"))
      (node (ref "P2") (pin "6") (pinfunction "6_6") (pintype "passive"))
      (node (ref "P3") (pin "6") (pinfunction "6_6") (pintype "passive"))
      (node (ref "P4") (pin "6") (pinfunction "6_6") (pintype "passive"))
      (node (ref "R8") (pin "2") (pinfunction "2_2") (pintype "passive"))
    )
    (net (code "61") (name "unconnected-(T1-Pad2)") (class "Default")
      (node (ref "T1") (pin "2") (pinfunction "2_2") (pintype "bidirectional"))
    )
    (net (code "62") (name "unconnected-(U2-3V3_EN-Pad37)") (class "Default")
      (node (ref "U2") (pin "37") (pinfunction "3V3_EN_37") (pintype "input"))
    )
    (net (code "63") (name "unconnected-(U2-ADC_REF-Pad35)") (class "Default")
      (node (ref "U2") (pin "35") (pinfunction "ADC_REF_35") (pintype "input"))
    )
    (net (code "64") (name "unconnected-(U2-GP2-Pad4)") (class "Default")
      (node (ref "U2") (pin "4") (pinfunction "GP2_4") (pintype "bidirectional"))
    )
    (net (code "65") (name "unconnected-(U2-GP3-Pad5)") (class "Default")
      (node (ref "U2") (pin "5") (pinfunction "GP3_5") (pintype "bidirectional"))
    )
    (net (code "66") (name "unconnected-(U2-GP22-Pad29)") (class "Default")
      (node (ref "U2") (pin "29") (pinfunction "GP22_29") (pintype "bidirectional"))
    )
    (net (code "67") (name "unconnected-(U2-GP28-Pad34)") (class "Default")
      (node (ref "U2") (pin "34") (pinfunction "GP28_34") (pintype "bidirectional"))
    )
    (net (code "68") (name "unconnected-(U2-RUN-Pad30)") (class "Default")
      (node (ref "U2") (pin "30") (pinfunction "RUN_30") (pintype "input"))
    )
    (net (code "69") (name "unconnected-(U2-SWCLK-Pad41)") (class "Default")
      (node (ref "U2") (pin "41") (pinfunction "SWCLK_41") (pintype "input"))
    )
    (net (code "70") (name "unconnected-(U2-SWDIO-Pad43)") (class "Default")
      (node (ref "U2") (pin "43") (pinfunction "SWDIO_43") (pintype "bidirectional"))
    )
  )
)
